# calculator.net
KiCad netlist of a schematic drawn in EAGLE
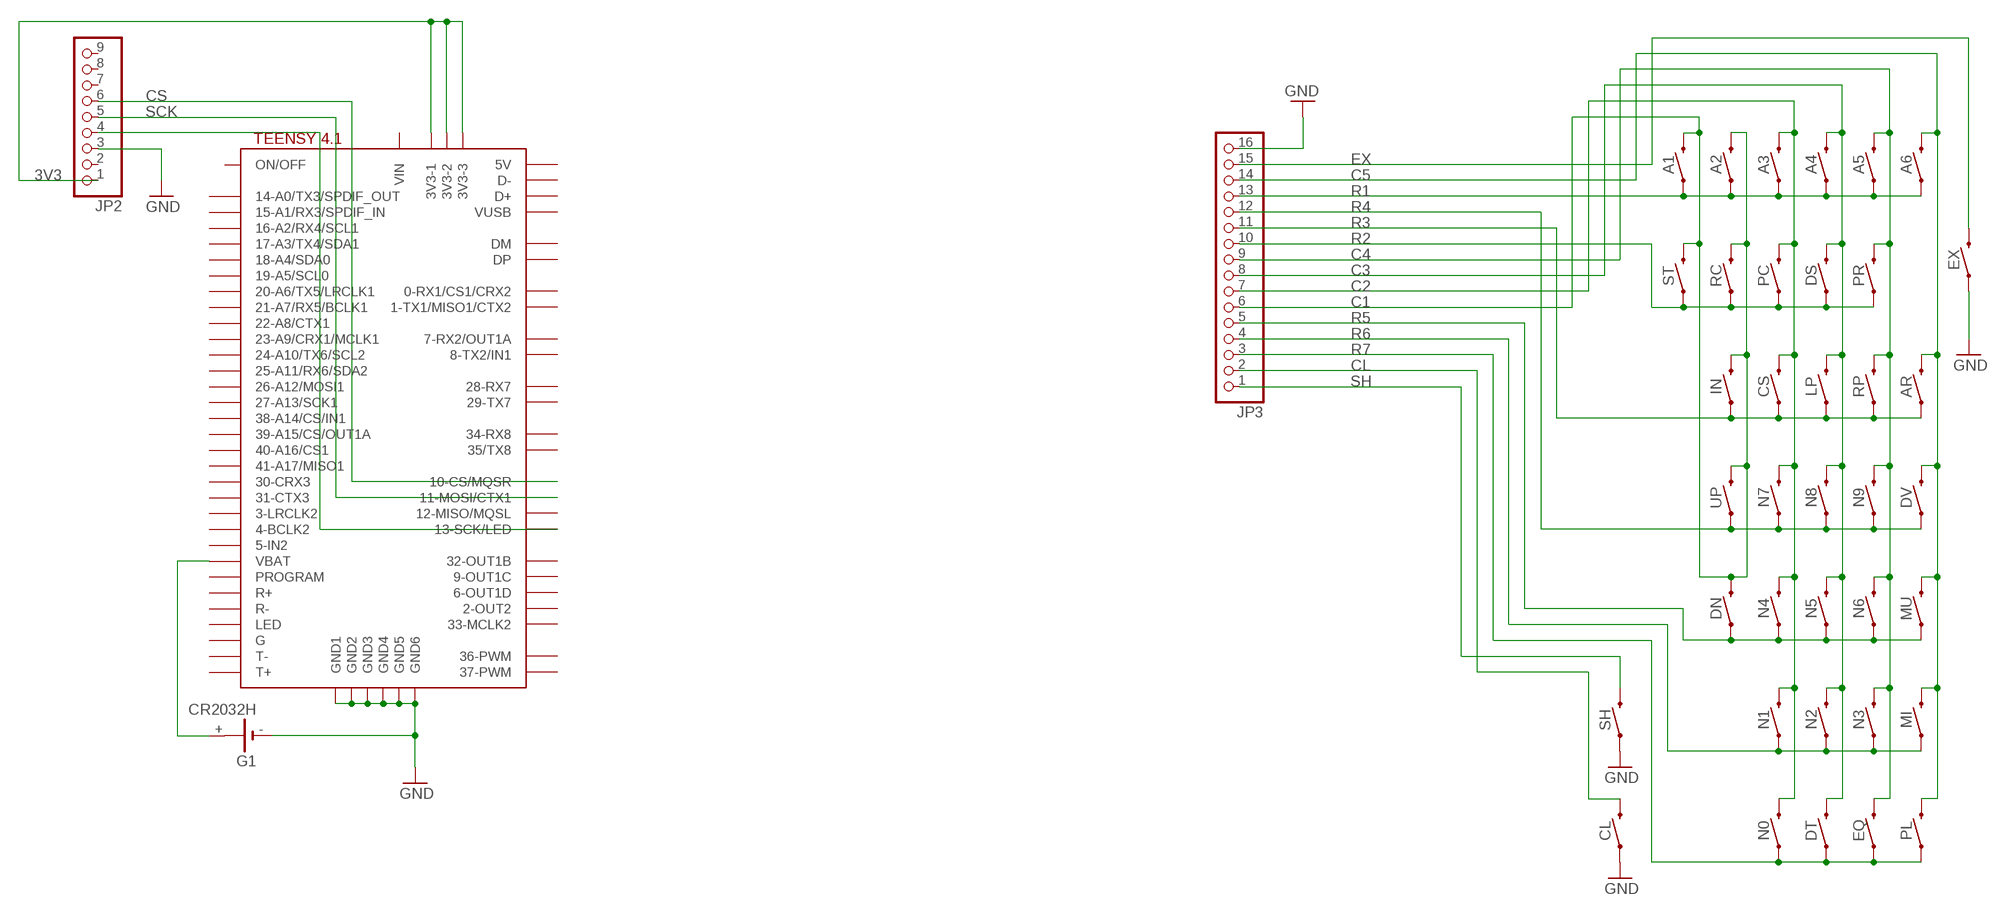
[diagram p0: schematic, sheet 1]

(export (version "E")
  (design (tool "Eeschema 10.0.6"))
  (components
    (comp (ref "A1")
      (value "MOMENTARY-SWITCH-SPST-PTH-6.0MM")
      (footprint "eagle-import:TACTILE_SWITCH_PTH_6.0MM")
      (libsource (lib "eagle-import") (part "MOMENTARY-SWITCH-SPST-PTH-6.0MM"))
    )
    (comp (ref "A2")
      (value "MOMENTARY-SWITCH-SPST-PTH-6.0MM")
      (footprint "eagle-import:TACTILE_SWITCH_PTH_6.0MM")
      (libsource (lib "eagle-import") (part "MOMENTARY-SWITCH-SPST-PTH-6.0MM"))
    )
    (comp (ref "A3")
      (value "MOMENTARY-SWITCH-SPST-PTH-6.0MM")
      (footprint "eagle-import:TACTILE_SWITCH_PTH_6.0MM")
      (libsource (lib "eagle-import") (part "MOMENTARY-SWITCH-SPST-PTH-6.0MM"))
    )
    (comp (ref "A4")
      (value "MOMENTARY-SWITCH-SPST-PTH-6.0MM")
      (footprint "eagle-import:TACTILE_SWITCH_PTH_6.0MM")
      (libsource (lib "eagle-import") (part "MOMENTARY-SWITCH-SPST-PTH-6.0MM"))
    )
    (comp (ref "A5")
      (value "MOMENTARY-SWITCH-SPST-PTH-6.0MM")
      (footprint "eagle-import:TACTILE_SWITCH_PTH_6.0MM")
      (libsource (lib "eagle-import") (part "MOMENTARY-SWITCH-SPST-PTH-6.0MM"))
    )
    (comp (ref "A6")
      (value "MOMENTARY-SWITCH-SPST-PTH-6.0MM")
      (footprint "eagle-import:TACTILE_SWITCH_PTH_6.0MM")
      (libsource (lib "eagle-import") (part "MOMENTARY-SWITCH-SPST-PTH-6.0MM"))
    )
    (comp (ref "AR")
      (value "MOMENTARY-SWITCH-SPST-PTH-6.0MM")
      (footprint "eagle-import:TACTILE_SWITCH_PTH_6.0MM")
      (libsource (lib "eagle-import") (part "MOMENTARY-SWITCH-SPST-PTH-6.0MM"))
    )
    (comp (ref "CL")
      (value "MOMENTARY-SWITCH-SPST-PTH-6.0MM")
      (footprint "eagle-import:TACTILE_SWITCH_PTH_6.0MM")
      (libsource (lib "eagle-import") (part "MOMENTARY-SWITCH-SPST-PTH-6.0MM"))
    )
    (comp (ref "CS")
      (value "MOMENTARY-SWITCH-SPST-PTH-6.0MM")
      (footprint "eagle-import:TACTILE_SWITCH_PTH_6.0MM")
      (libsource (lib "eagle-import") (part "MOMENTARY-SWITCH-SPST-PTH-6.0MM"))
    )
    (comp (ref "DN")
      (value "MOMENTARY-SWITCH-SPST-PTH-6.0MM")
      (footprint "eagle-import:TACTILE_SWITCH_PTH_6.0MM")
      (libsource (lib "eagle-import") (part "MOMENTARY-SWITCH-SPST-PTH-6.0MM"))
    )
    (comp (ref "DS")
      (value "MOMENTARY-SWITCH-SPST-PTH-6.0MM")
      (footprint "eagle-import:TACTILE_SWITCH_PTH_6.0MM")
      (libsource (lib "eagle-import") (part "MOMENTARY-SWITCH-SPST-PTH-6.0MM"))
    )
    (comp (ref "DT")
      (value "MOMENTARY-SWITCH-SPST-PTH-6.0MM")
      (footprint "eagle-import:TACTILE_SWITCH_PTH_6.0MM")
      (libsource (lib "eagle-import") (part "MOMENTARY-SWITCH-SPST-PTH-6.0MM"))
    )
    (comp (ref "DV")
      (value "MOMENTARY-SWITCH-SPST-PTH-6.0MM")
      (footprint "eagle-import:TACTILE_SWITCH_PTH_6.0MM")
      (libsource (lib "eagle-import") (part "MOMENTARY-SWITCH-SPST-PTH-6.0MM"))
    )
    (comp (ref "EQ")
      (value "MOMENTARY-SWITCH-SPST-PTH-6.0MM")
      (footprint "eagle-import:TACTILE_SWITCH_PTH_6.0MM")
      (libsource (lib "eagle-import") (part "MOMENTARY-SWITCH-SPST-PTH-6.0MM"))
    )
    (comp (ref "EX")
      (value "MOMENTARY-SWITCH-SPST-PTH-6.0MM")
      (footprint "eagle-import:TACTILE_SWITCH_PTH_6.0MM")
      (libsource (lib "eagle-import") (part "MOMENTARY-SWITCH-SPST-PTH-6.0MM"))
    )
    (comp (ref "G1")
      (value "CR2032H")
      (footprint "eagle-import:CR2032H")
      (libsource (lib "eagle-import") (part "CR2032H"))
    )
    (comp (ref "IN")
      (value "MOMENTARY-SWITCH-SPST-PTH-6.0MM")
      (footprint "eagle-import:TACTILE_SWITCH_PTH_6.0MM")
      (libsource (lib "eagle-import") (part "MOMENTARY-SWITCH-SPST-PTH-6.0MM"))
    )
    (comp (ref "JP2")
      (value "PINHD-1X9")
      (footprint "eagle-import:1X09-BIG")
      (libsource (lib "eagle-import") (part "PINHD-1X9"))
    )
    (comp (ref "JP3")
      (value "PINHD-1X16")
      (footprint "eagle-import:1X16")
      (libsource (lib "eagle-import") (part "PINHD-1X16"))
    )
    (comp (ref "LP")
      (value "MOMENTARY-SWITCH-SPST-PTH-6.0MM")
      (footprint "eagle-import:TACTILE_SWITCH_PTH_6.0MM")
      (libsource (lib "eagle-import") (part "MOMENTARY-SWITCH-SPST-PTH-6.0MM"))
    )
    (comp (ref "MI")
      (value "MOMENTARY-SWITCH-SPST-PTH-6.0MM")
      (footprint "eagle-import:TACTILE_SWITCH_PTH_6.0MM")
      (libsource (lib "eagle-import") (part "MOMENTARY-SWITCH-SPST-PTH-6.0MM"))
    )
    (comp (ref "MU")
      (value "MOMENTARY-SWITCH-SPST-PTH-6.0MM")
      (footprint "eagle-import:TACTILE_SWITCH_PTH_6.0MM")
      (libsource (lib "eagle-import") (part "MOMENTARY-SWITCH-SPST-PTH-6.0MM"))
    )
    (comp (ref "N0")
      (value "MOMENTARY-SWITCH-SPST-PTH-6.0MM")
      (footprint "eagle-import:TACTILE_SWITCH_PTH_6.0MM")
      (libsource (lib "eagle-import") (part "MOMENTARY-SWITCH-SPST-PTH-6.0MM"))
    )
    (comp (ref "N1")
      (value "MOMENTARY-SWITCH-SPST-PTH-6.0MM")
      (footprint "eagle-import:TACTILE_SWITCH_PTH_6.0MM")
      (libsource (lib "eagle-import") (part "MOMENTARY-SWITCH-SPST-PTH-6.0MM"))
    )
    (comp (ref "N2")
      (value "MOMENTARY-SWITCH-SPST-PTH-6.0MM")
      (footprint "eagle-import:TACTILE_SWITCH_PTH_6.0MM")
      (libsource (lib "eagle-import") (part "MOMENTARY-SWITCH-SPST-PTH-6.0MM"))
    )
    (comp (ref "N3")
      (value "MOMENTARY-SWITCH-SPST-PTH-6.0MM")
      (footprint "eagle-import:TACTILE_SWITCH_PTH_6.0MM")
      (libsource (lib "eagle-import") (part "MOMENTARY-SWITCH-SPST-PTH-6.0MM"))
    )
    (comp (ref "N4")
      (value "MOMENTARY-SWITCH-SPST-PTH-6.0MM")
      (footprint "eagle-import:TACTILE_SWITCH_PTH_6.0MM")
      (libsource (lib "eagle-import") (part "MOMENTARY-SWITCH-SPST-PTH-6.0MM"))
    )
    (comp (ref "N5")
      (value "MOMENTARY-SWITCH-SPST-PTH-6.0MM")
      (footprint "eagle-import:TACTILE_SWITCH_PTH_6.0MM")
      (libsource (lib "eagle-import") (part "MOMENTARY-SWITCH-SPST-PTH-6.0MM"))
    )
    (comp (ref "N6")
      (value "MOMENTARY-SWITCH-SPST-PTH-6.0MM")
      (footprint "eagle-import:TACTILE_SWITCH_PTH_6.0MM")
      (libsource (lib "eagle-import") (part "MOMENTARY-SWITCH-SPST-PTH-6.0MM"))
    )
    (comp (ref "N7")
      (value "MOMENTARY-SWITCH-SPST-PTH-6.0MM")
      (footprint "eagle-import:TACTILE_SWITCH_PTH_6.0MM")
      (libsource (lib "eagle-import") (part "MOMENTARY-SWITCH-SPST-PTH-6.0MM"))
    )
    (comp (ref "N8")
      (value "MOMENTARY-SWITCH-SPST-PTH-6.0MM")
      (footprint "eagle-import:TACTILE_SWITCH_PTH_6.0MM")
      (libsource (lib "eagle-import") (part "MOMENTARY-SWITCH-SPST-PTH-6.0MM"))
    )
    (comp (ref "N9")
      (value "MOMENTARY-SWITCH-SPST-PTH-6.0MM")
      (footprint "eagle-import:TACTILE_SWITCH_PTH_6.0MM")
      (libsource (lib "eagle-import") (part "MOMENTARY-SWITCH-SPST-PTH-6.0MM"))
    )
    (comp (ref "PC")
      (value "MOMENTARY-SWITCH-SPST-PTH-6.0MM")
      (footprint "eagle-import:TACTILE_SWITCH_PTH_6.0MM")
      (libsource (lib "eagle-import") (part "MOMENTARY-SWITCH-SPST-PTH-6.0MM"))
    )
    (comp (ref "PL")
      (value "MOMENTARY-SWITCH-SPST-PTH-6.0MM")
      (footprint "eagle-import:TACTILE_SWITCH_PTH_6.0MM")
      (libsource (lib "eagle-import") (part "MOMENTARY-SWITCH-SPST-PTH-6.0MM"))
    )
    (comp (ref "PR")
      (value "MOMENTARY-SWITCH-SPST-PTH-6.0MM")
      (footprint "eagle-import:TACTILE_SWITCH_PTH_6.0MM")
      (libsource (lib "eagle-import") (part "MOMENTARY-SWITCH-SPST-PTH-6.0MM"))
    )
    (comp (ref "RC")
      (value "MOMENTARY-SWITCH-SPST-PTH-6.0MM")
      (footprint "eagle-import:TACTILE_SWITCH_PTH_6.0MM")
      (libsource (lib "eagle-import") (part "MOMENTARY-SWITCH-SPST-PTH-6.0MM"))
    )
    (comp (ref "RP")
      (value "MOMENTARY-SWITCH-SPST-PTH-6.0MM")
      (footprint "eagle-import:TACTILE_SWITCH_PTH_6.0MM")
      (libsource (lib "eagle-import") (part "MOMENTARY-SWITCH-SPST-PTH-6.0MM"))
    )
    (comp (ref "SH")
      (value "MOMENTARY-SWITCH-SPST-PTH-6.0MM")
      (footprint "eagle-import:TACTILE_SWITCH_PTH_6.0MM")
      (libsource (lib "eagle-import") (part "MOMENTARY-SWITCH-SPST-PTH-6.0MM"))
    )
    (comp (ref "ST")
      (value "MOMENTARY-SWITCH-SPST-PTH-6.0MM")
      (footprint "eagle-import:TACTILE_SWITCH_PTH_6.0MM")
      (libsource (lib "eagle-import") (part "MOMENTARY-SWITCH-SPST-PTH-6.0MM"))
    )
    (comp (ref "U$1")
      (value "TEENSY41")
      (footprint "eagle-import:TEENSY41")
      (libsource (lib "eagle-import") (part "TEENSY41"))
    )
    (comp (ref "UP")
      (value "MOMENTARY-SWITCH-SPST-PTH-6.0MM")
      (footprint "eagle-import:TACTILE_SWITCH_PTH_6.0MM")
      (libsource (lib "eagle-import") (part "MOMENTARY-SWITCH-SPST-PTH-6.0MM"))
    )
  )
  (nets
    (net (code "1") (name "/3V3") (class "Default")
      (node (ref "JP2") (pin "1") (pinfunction "1_1") (pintype "passive"))
      (node (ref "U$1") (pin "3V3-1") (pinfunction "3V3-1_3V3-1") (pintype "bidirectional"))
      (node (ref "U$1") (pin "3V3-2") (pinfunction "3V3-2_3V3-2") (pintype "bidirectional"))
      (node (ref "U$1") (pin "3V3-3") (pinfunction "3V3-3_3V3-3") (pintype "bidirectional"))
    )
    (net (code "2") (name "/C1") (class "Default")
      (node (ref "A1") (pin "3") (pinfunction "2_3") (pintype "passive"))
      (node (ref "A2") (pin "3") (pinfunction "2_3") (pintype "passive"))
      (node (ref "DN") (pin "3") (pinfunction "2_3") (pintype "passive"))
      (node (ref "IN") (pin "3") (pinfunction "2_3") (pintype "passive"))
      (node (ref "JP3") (pin "6") (pinfunction "6_6") (pintype "passive"))
      (node (ref "RC") (pin "3") (pinfunction "2_3") (pintype "passive"))
      (node (ref "ST") (pin "3") (pinfunction "2_3") (pintype "passive"))
      (node (ref "UP") (pin "3") (pinfunction "2_3") (pintype "passive"))
    )
    (net (code "3") (name "/C2") (class "Default")
      (node (ref "A3") (pin "3") (pinfunction "2_3") (pintype "passive"))
      (node (ref "CS") (pin "3") (pinfunction "2_3") (pintype "passive"))
      (node (ref "JP3") (pin "7") (pinfunction "7_7") (pintype "passive"))
      (node (ref "N0") (pin "3") (pinfunction "2_3") (pintype "passive"))
      (node (ref "N1") (pin "3") (pinfunction "2_3") (pintype "passive"))
      (node (ref "N4") (pin "3") (pinfunction "2_3") (pintype "passive"))
      (node (ref "N7") (pin "3") (pinfunction "2_3") (pintype "passive"))
      (node (ref "PC") (pin "3") (pinfunction "2_3") (pintype "passive"))
    )
    (net (code "4") (name "/C3") (class "Default")
      (node (ref "A4") (pin "3") (pinfunction "2_3") (pintype "passive"))
      (node (ref "DS") (pin "3") (pinfunction "2_3") (pintype "passive"))
      (node (ref "DT") (pin "3") (pinfunction "2_3") (pintype "passive"))
      (node (ref "JP3") (pin "8") (pinfunction "8_8") (pintype "passive"))
      (node (ref "LP") (pin "3") (pinfunction "2_3") (pintype "passive"))
      (node (ref "N2") (pin "3") (pinfunction "2_3") (pintype "passive"))
      (node (ref "N5") (pin "3") (pinfunction "2_3") (pintype "passive"))
      (node (ref "N8") (pin "3") (pinfunction "2_3") (pintype "passive"))
    )
    (net (code "5") (name "/C4") (class "Default")
      (node (ref "A5") (pin "3") (pinfunction "2_3") (pintype "passive"))
      (node (ref "EQ") (pin "3") (pinfunction "2_3") (pintype "passive"))
      (node (ref "JP3") (pin "9") (pinfunction "9_9") (pintype "passive"))
      (node (ref "N3") (pin "3") (pinfunction "2_3") (pintype "passive"))
      (node (ref "N6") (pin "3") (pinfunction "2_3") (pintype "passive"))
      (node (ref "N9") (pin "3") (pinfunction "2_3") (pintype "passive"))
      (node (ref "PR") (pin "3") (pinfunction "2_3") (pintype "passive"))
      (node (ref "RP") (pin "3") (pinfunction "2_3") (pintype "passive"))
    )
    (net (code "6") (name "/C5") (class "Default")
      (node (ref "A6") (pin "3") (pinfunction "2_3") (pintype "passive"))
      (node (ref "AR") (pin "3") (pinfunction "2_3") (pintype "passive"))
      (node (ref "DV") (pin "3") (pinfunction "2_3") (pintype "passive"))
      (node (ref "JP3") (pin "14") (pinfunction "14_14") (pintype "passive"))
      (node (ref "MI") (pin "3") (pinfunction "2_3") (pintype "passive"))
      (node (ref "MU") (pin "3") (pinfunction "2_3") (pintype "passive"))
      (node (ref "PL") (pin "3") (pinfunction "2_3") (pintype "passive"))
    )
    (net (code "7") (name "/CL") (class "Default")
      (node (ref "CL") (pin "3") (pinfunction "2_3") (pintype "passive"))
      (node (ref "JP3") (pin "2") (pinfunction "2_2") (pintype "passive"))
    )
    (net (code "8") (name "/CS") (class "Default")
      (node (ref "JP2") (pin "6") (pinfunction "6_6") (pintype "passive"))
      (node (ref "U$1") (pin "10-CS\\MQSR") (pinfunction "10-CS/MQSR_10-CS\\MQSR") (pintype "bidirectional"))
    )
    (net (code "9") (name "/EX") (class "Default")
      (node (ref "EX") (pin "3") (pinfunction "2_3") (pintype "passive"))
      (node (ref "JP3") (pin "15") (pinfunction "15_15") (pintype "passive"))
    )
    (net (code "10") (name "/R1") (class "Default")
      (node (ref "A1") (pin "1") (pinfunction "1_1") (pintype "passive"))
      (node (ref "A2") (pin "1") (pinfunction "1_1") (pintype "passive"))
      (node (ref "A3") (pin "1") (pinfunction "1_1") (pintype "passive"))
      (node (ref "A4") (pin "1") (pinfunction "1_1") (pintype "passive"))
      (node (ref "A5") (pin "1") (pinfunction "1_1") (pintype "passive"))
      (node (ref "A6") (pin "1") (pinfunction "1_1") (pintype "passive"))
      (node (ref "JP3") (pin "13") (pinfunction "13_13") (pintype "passive"))
    )
    (net (code "11") (name "/R2") (class "Default")
      (node (ref "DS") (pin "1") (pinfunction "1_1") (pintype "passive"))
      (node (ref "JP3") (pin "10") (pinfunction "10_10") (pintype "passive"))
      (node (ref "PC") (pin "1") (pinfunction "1_1") (pintype "passive"))
      (node (ref "PR") (pin "1") (pinfunction "1_1") (pintype "passive"))
      (node (ref "RC") (pin "1") (pinfunction "1_1") (pintype "passive"))
      (node (ref "ST") (pin "1") (pinfunction "1_1") (pintype "passive"))
    )
    (net (code "12") (name "/R3") (class "Default")
      (node (ref "AR") (pin "1") (pinfunction "1_1") (pintype "passive"))
      (node (ref "CS") (pin "1") (pinfunction "1_1") (pintype "passive"))
      (node (ref "IN") (pin "1") (pinfunction "1_1") (pintype "passive"))
      (node (ref "JP3") (pin "11") (pinfunction "11_11") (pintype "passive"))
      (node (ref "LP") (pin "1") (pinfunction "1_1") (pintype "passive"))
      (node (ref "RP") (pin "1") (pinfunction "1_1") (pintype "passive"))
    )
    (net (code "13") (name "/R4") (class "Default")
      (node (ref "DV") (pin "1") (pinfunction "1_1") (pintype "passive"))
      (node (ref "JP3") (pin "12") (pinfunction "12_12") (pintype "passive"))
      (node (ref "N7") (pin "1") (pinfunction "1_1") (pintype "passive"))
      (node (ref "N8") (pin "1") (pinfunction "1_1") (pintype "passive"))
      (node (ref "N9") (pin "1") (pinfunction "1_1") (pintype "passive"))
      (node (ref "UP") (pin "1") (pinfunction "1_1") (pintype "passive"))
    )
    (net (code "14") (name "/R5") (class "Default")
      (node (ref "DN") (pin "1") (pinfunction "1_1") (pintype "passive"))
      (node (ref "JP3") (pin "5") (pinfunction "5_5") (pintype "passive"))
      (node (ref "MU") (pin "1") (pinfunction "1_1") (pintype "passive"))
      (node (ref "N4") (pin "1") (pinfunction "1_1") (pintype "passive"))
      (node (ref "N5") (pin "1") (pinfunction "1_1") (pintype "passive"))
      (node (ref "N6") (pin "1") (pinfunction "1_1") (pintype "passive"))
    )
    (net (code "15") (name "/R6") (class "Default")
      (node (ref "JP3") (pin "4") (pinfunction "4_4") (pintype "passive"))
      (node (ref "MI") (pin "1") (pinfunction "1_1") (pintype "passive"))
      (node (ref "N1") (pin "1") (pinfunction "1_1") (pintype "passive"))
      (node (ref "N2") (pin "1") (pinfunction "1_1") (pintype "passive"))
      (node (ref "N3") (pin "1") (pinfunction "1_1") (pintype "passive"))
    )
    (net (code "16") (name "/R7") (class "Default")
      (node (ref "DT") (pin "1") (pinfunction "1_1") (pintype "passive"))
      (node (ref "EQ") (pin "1") (pinfunction "1_1") (pintype "passive"))
      (node (ref "JP3") (pin "3") (pinfunction "3_3") (pintype "passive"))
      (node (ref "N0") (pin "1") (pinfunction "1_1") (pintype "passive"))
      (node (ref "PL") (pin "1") (pinfunction "1_1") (pintype "passive"))
    )
    (net (code "17") (name "/SCK") (class "Default")
      (node (ref "JP2") (pin "4") (pinfunction "4_4") (pintype "passive"))
      (node (ref "U$1") (pin "13-SCK/LED") (pinfunction "13-SCK/LED_13-SCK/LED") (pintype "bidirectional"))
    )
    (net (code "18") (name "/SH") (class "Default")
      (node (ref "JP3") (pin "1") (pinfunction "1_1") (pintype "passive"))
      (node (ref "SH") (pin "3") (pinfunction "2_3") (pintype "passive"))
    )
    (net (code "19") (name "GND") (class "Default")
      (node (ref "CL") (pin "1") (pinfunction "1_1") (pintype "passive"))
      (node (ref "EX") (pin "1") (pinfunction "1_1") (pintype "passive"))
      (node (ref "G1") (pin "-") (pinfunction "-_-") (pintype "passive"))
      (node (ref "JP2") (pin "3") (pinfunction "3_3") (pintype "passive"))
      (node (ref "JP3") (pin "16") (pinfunction "16_16") (pintype "passive"))
      (node (ref "SH") (pin "1") (pinfunction "1_1") (pintype "passive"))
      (node (ref "U$1") (pin "GND1") (pinfunction "GND1_GND1") (pintype "bidirectional"))
      (node (ref "U$1") (pin "GND2") (pinfunction "GND2_GND2") (pintype "bidirectional"))
      (node (ref "U$1") (pin "GND3") (pinfunction "GND3_GND3") (pintype "bidirectional"))
      (node (ref "U$1") (pin "GND4") (pinfunction "GND4_GND4") (pintype "bidirectional"))
      (node (ref "U$1") (pin "GND5") (pinfunction "GND5_GND5") (pintype "bidirectional"))
      (node (ref "U$1") (pin "GND6") (pinfunction "GND6_GND6") (pintype "bidirectional"))
    )
    (net (code "20") (name "Net-(G1-Pad+)") (class "Default")
      (node (ref "G1") (pin "+") (pinfunction "+_+") (pintype "passive"))
      (node (ref "U$1") (pin "VBAT") (pinfunction "VBAT_VBAT") (pintype "bidirectional"))
    )
    (net (code "21") (name "Net-(JP2-Pad5)") (class "Default")
      (node (ref "JP2") (pin "5") (pinfunction "5_5") (pintype "passive"))
      (node (ref "U$1") (pin "11-MOSI/CTX1") (pinfunction "11-MOSI/CTX1_11-MOSI/CTX1") (pintype "bidirectional"))
    )
    (net (code "22") (name "unconnected-(G1-+-Pad+@1)") (class "Default")
      (node (ref "G1") (pin "+@1") (pinfunction "+_+@1") (pintype "passive"))
    )
    (net (code "23") (name "unconnected-(JP2-Pad2)") (class "Default")
      (node (ref "JP2") (pin "2") (pinfunction "2_2") (pintype "passive"))
    )
    (net (code "24") (name "unconnected-(JP2-Pad7)") (class "Default")
      (node (ref "JP2") (pin "7") (pinfunction "7_7") (pintype "passive"))
    )
    (net (code "25") (name "unconnected-(JP2-Pad8)") (class "Default")
      (node (ref "JP2") (pin "8") (pinfunction "8_8") (pintype "passive"))
    )
    (net (code "26") (name "unconnected-(JP2-Pad9)") (class "Default")
      (node (ref "JP2") (pin "9") (pinfunction "9_9") (pintype "passive"))
    )
    (net (code "27") (name "unconnected-(U$1-5V-Pad+5V)") (class "Default")
      (node (ref "U$1") (pin "+5V") (pinfunction "5V_+5V") (pintype "bidirectional"))
    )
    (net (code "28") (name "unconnected-(U$1-8-TX2{slash}IN1-Pad8-TX2{slash}IN2)") (class "Default")
      (node (ref "U$1") (pin "8-TX2/IN2") (pinfunction "8-TX2/IN1_8-TX2/IN2") (pintype "bidirectional"))
    )
    (net (code "29") (name "unconnected-(U$1-35{slash}TX8-Pad35-TX8)") (class "Default")
      (node (ref "U$1") (pin "35-TX8") (pinfunction "35/TX8_35-TX8") (pintype "bidirectional"))
    )
    (net (code "30") (name "unconnected-(U$1-Pad0-RX1{slash}CS1{slash}CRX2)") (class "Default")
      (node (ref "U$1") (pin "0-RX1/CS1/CRX2") (pinfunction "0-RX1/CS1/CRX2_0-RX1/CS1/CRX2") (pintype "bidirectional"))
    )
    (net (code "31") (name "unconnected-(U$1-Pad1-TX1{slash}MISO1{slash}CTX2)") (class "Default")
      (node (ref "U$1") (pin "1-TX1/MISO1/CTX2") (pinfunction "1-TX1/MISO1/CTX2_1-TX1/MISO1/CTX2") (pintype "bidirectional"))
    )
    (net (code "32") (name "unconnected-(U$1-Pad2-OUT2)") (class "Default")
      (node (ref "U$1") (pin "2-OUT2") (pinfunction "2-OUT2_2-OUT2") (pintype "bidirectional"))
    )
    (net (code "33") (name "unconnected-(U$1-Pad3-LRCLK2)") (class "Default")
      (node (ref "U$1") (pin "3-LRCLK2") (pinfunction "3-LRCLK2_3-LRCLK2") (pintype "bidirectional"))
    )
    (net (code "34") (name "unconnected-(U$1-Pad4-BCLK2)") (class "Default")
      (node (ref "U$1") (pin "4-BCLK2") (pinfunction "4-BCLK2_4-BCLK2") (pintype "bidirectional"))
    )
    (net (code "35") (name "unconnected-(U$1-Pad5-IN2)") (class "Default")
      (node (ref "U$1") (pin "5-IN2") (pinfunction "5-IN2_5-IN2") (pintype "bidirectional"))
    )
    (net (code "36") (name "unconnected-(U$1-Pad6-OUT1D)") (class "Default")
      (node (ref "U$1") (pin "6-OUT1D") (pinfunction "6-OUT1D_6-OUT1D") (pintype "bidirectional"))
    )
    (net (code "37") (name "unconnected-(U$1-Pad7-RX2{slash}OUT1A)") (class "Default")
      (node (ref "U$1") (pin "7-RX2/OUT1A") (pinfunction "7-RX2/OUT1A_7-RX2/OUT1A") (pintype "bidirectional"))
    )
    (net (code "38") (name "unconnected-(U$1-Pad9-OUT1C)") (class "Default")
      (node (ref "U$1") (pin "9-OUT1C") (pinfunction "9-OUT1C_9-OUT1C") (pintype "bidirectional"))
    )
    (net (code "39") (name "unconnected-(U$1-Pad12-MISO{slash}MQSL)") (class "Default")
      (node (ref "U$1") (pin "12-MISO/MQSL") (pinfunction "12-MISO/MQSL_12-MISO/MQSL") (pintype "bidirectional"))
    )
    (net (code "40") (name "unconnected-(U$1-Pad14-A0{slash}TX3{slash}SPDIF_OUT)") (class "Default")
      (node (ref "U$1") (pin "14-A0/TX3/SPDIF_OUT") (pinfunction "14-A0/TX3/SPDIF_OUT_14-A0/TX3/SPDIF_OUT") (pintype "bidirectional"))
    )
    (net (code "41") (name "unconnected-(U$1-Pad15-A1{slash}RX3{slash}SPDIF_IN)") (class "Default")
      (node (ref "U$1") (pin "15-A1/RX3/SPDIF_IN") (pinfunction "15-A1/RX3/SPDIF_IN_15-A1/RX3/SPDIF_IN") (pintype "bidirectional"))
    )
    (net (code "42") (name "unconnected-(U$1-Pad16-A2{slash}RX4{slash}SCL1)") (class "Default")
      (node (ref "U$1") (pin "16-A2/RX4/SCL1") (pinfunction "16-A2/RX4/SCL1_16-A2/RX4/SCL1") (pintype "bidirectional"))
    )
    (net (code "43") (name "unconnected-(U$1-Pad17-A3{slash}TX4{slash}SDA1)") (class "Default")
      (node (ref "U$1") (pin "17-A3/TX4/SDA1") (pinfunction "17-A3/TX4/SDA1_17-A3/TX4/SDA1") (pintype "bidirectional"))
    )
    (net (code "44") (name "unconnected-(U$1-Pad18-A4{slash}SDA0)") (class "Default")
      (node (ref "U$1") (pin "18-A4/SDA0") (pinfunction "18-A4/SDA0_18-A4/SDA0") (pintype "bidirectional"))
    )
    (net (code "45") (name "unconnected-(U$1-Pad19-A5{slash}SCL0)") (class "Default")
      (node (ref "U$1") (pin "19-A5/SCL0") (pinfunction "19-A5/SCL0_19-A5/SCL0") (pintype "bidirectional"))
    )
    (net (code "46") (name "unconnected-(U$1-Pad20-A6{slash}TX5{slash}LRCLK1)") (class "Default")
      (node (ref "U$1") (pin "20-A6/TX5/LRCLK1") (pinfunction "20-A6/TX5/LRCLK1_20-A6/TX5/LRCLK1") (pintype "bidirectional"))
    )
    (net (code "47") (name "unconnected-(U$1-Pad21-A7{slash}RX5{slash}BCLK1)") (class "Default")
      (node (ref "U$1") (pin "21-A7/RX5/BCLK1") (pinfunction "21-A7/RX5/BCLK1_21-A7/RX5/BCLK1") (pintype "bidirectional"))
    )
    (net (code "48") (name "unconnected-(U$1-Pad22-A8{slash}CTX1)") (class "Default")
      (node (ref "U$1") (pin "22-A8/CTX1") (pinfunction "22-A8/CTX1_22-A8/CTX1") (pintype "bidirectional"))
    )
    (net (code "49") (name "unconnected-(U$1-Pad23-A9{slash}CRX1{slash}MCLK1)") (class "Default")
      (node (ref "U$1") (pin "23-A9/CRX1/MCLK1") (pinfunction "23-A9/CRX1/MCLK1_23-A9/CRX1/MCLK1") (pintype "bidirectional"))
    )
    (net (code "50") (name "unconnected-(U$1-Pad24-A10{slash}TX6{slash}SCL2)") (class "Default")
      (node (ref "U$1") (pin "24-A10/TX6/SCL2") (pinfunction "24-A10/TX6/SCL2_24-A10/TX6/SCL2") (pintype "bidirectional"))
    )
    (net (code "51") (name "unconnected-(U$1-Pad25-A11{slash}RX6{slash}SDA2)") (class "Default")
      (node (ref "U$1") (pin "25-A11/RX6/SDA2") (pinfunction "25-A11/RX6/SDA2_25-A11/RX6/SDA2") (pintype "bidirectional"))
    )
    (net (code "52") (name "unconnected-(U$1-Pad26-A12{slash}MOSI1)") (class "Default")
      (node (ref "U$1") (pin "26-A12/MOSI1") (pinfunction "26-A12/MOSI1_26-A12/MOSI1") (pintype "bidirectional"))
    )
    (net (code "53") (name "unconnected-(U$1-Pad27-A13{slash}SCK1)") (class "Default")
      (node (ref "U$1") (pin "27-A13/SCK1") (pinfunction "27-A13/SCK1_27-A13/SCK1") (pintype "bidirectional"))
    )
    (net (code "54") (name "unconnected-(U$1-Pad28-RX7)") (class "Default")
      (node (ref "U$1") (pin "28-RX7") (pinfunction "28-RX7_28-RX7") (pintype "bidirectional"))
    )
    (net (code "55") (name "unconnected-(U$1-Pad29-TX7)") (class "Default")
      (node (ref "U$1") (pin "29-TX7") (pinfunction "29-TX7_29-TX7") (pintype "bidirectional"))
    )
    (net (code "56") (name "unconnected-(U$1-Pad30-CRX3)") (class "Default")
      (node (ref "U$1") (pin "30-CRX3") (pinfunction "30-CRX3_30-CRX3") (pintype "bidirectional"))
    )
    (net (code "57") (name "unconnected-(U$1-Pad31-CTX3)") (class "Default")
      (node (ref "U$1") (pin "31-CTX3") (pinfunction "31-CTX3_31-CTX3") (pintype "bidirectional"))
    )
    (net (code "58") (name "unconnected-(U$1-Pad32-OUT1B)") (class "Default")
      (node (ref "U$1") (pin "32-OUT1B") (pinfunction "32-OUT1B_32-OUT1B") (pintype "bidirectional"))
    )
    (net (code "59") (name "unconnected-(U$1-Pad33-MCLK2)") (class "Default")
      (node (ref "U$1") (pin "33-MCLK2") (pinfunction "33-MCLK2_33-MCLK2") (pintype "bidirectional"))
    )
    (net (code "60") (name "unconnected-(U$1-Pad34-RX8)") (class "Default")
      (node (ref "U$1") (pin "34-RX8") (pinfunction "34-RX8_34-RX8") (pintype "bidirectional"))
    )
    (net (code "61") (name "unconnected-(U$1-Pad36-PWM)") (class "Default")
      (node (ref "U$1") (pin "36-PWM") (pinfunction "36-PWM_36-PWM") (pintype "bidirectional"))
    )
    (net (code "62") (name "unconnected-(U$1-Pad37-PWM)") (class "Default")
      (node (ref "U$1") (pin "37-PWM") (pinfunction "37-PWM_37-PWM") (pintype "bidirectional"))
    )
    (net (code "63") (name "unconnected-(U$1-Pad38-A14{slash}CS{slash}IN1)") (class "Default")
      (node (ref "U$1") (pin "38-A14/CS/IN1") (pinfunction "38-A14/CS/IN1_38-A14/CS/IN1") (pintype "bidirectional"))
    )
    (net (code "64") (name "unconnected-(U$1-Pad39-A15{slash}CS{slash}OUT1A)") (class "Default")
      (node (ref "U$1") (pin "39-A15/CS/OUT1A") (pinfunction "39-A15/CS/OUT1A_39-A15/CS/OUT1A") (pintype "bidirectional"))
    )
    (net (code "65") (name "unconnected-(U$1-Pad40-A16{slash}CS1)") (class "Default")
      (node (ref "U$1") (pin "40-A16/CS1") (pinfunction "40-A16/CS1_40-A16/CS1") (pintype "bidirectional"))
    )
    (net (code "66") (name "unconnected-(U$1-Pad41-A17{slash}MISO1)") (class "Default")
      (node (ref "U$1") (pin "41-A17/MISO1") (pinfunction "41-A17/MISO1_41-A17/MISO1") (pintype "bidirectional"))
    )
    (net (code "67") (name "unconnected-(U$1-PadD+)") (class "Default")
      (node (ref "U$1") (pin "D+") (pinfunction "D+_D+") (pintype "bidirectional"))
    )
    (net (code "68") (name "unconnected-(U$1-PadD-)") (class "Default")
      (node (ref "U$1") (pin "D-") (pinfunction "D-_D-") (pintype "bidirectional"))
    )
    (net (code "69") (name "unconnected-(U$1-PadDM)") (class "Default")
      (node (ref "U$1") (pin "DM") (pinfunction "DM_DM") (pintype "bidirectional"))
    )
    (net (code "70") (name "unconnected-(U$1-PadDP)") (class "Default")
      (node (ref "U$1") (pin "DP") (pinfunction "DP_DP") (pintype "bidirectional"))
    )
    (net (code "71") (name "unconnected-(U$1-PadG)") (class "Default")
      (node (ref "U$1") (pin "G") (pinfunction "G_G") (pintype "bidirectional"))
    )
    (net (code "72") (name "unconnected-(U$1-PadLED)") (class "Default")
      (node (ref "U$1") (pin "LED") (pinfunction "LED_LED") (pintype "bidirectional"))
    )
    (net (code "73") (name "unconnected-(U$1-PadON{slash}OFF)") (class "Default")
      (node (ref "U$1") (pin "ON/OFF") (pinfunction "ON/OFF_ON/OFF") (pintype "bidirectional"))
    )
    (net (code "74") (name "unconnected-(U$1-PadPROGRAM)") (class "Default")
      (node (ref "U$1") (pin "PROGRAM") (pinfunction "PROGRAM_PROGRAM") (pintype "bidirectional"))
    )
    (net (code "75") (name "unconnected-(U$1-PadR+)") (class "Default")
      (node (ref "U$1") (pin "R+") (pinfunction "R+_R+") (pintype "bidirectional"))
    )
    (net (code "76") (name "unconnected-(U$1-PadR-)") (class "Default")
      (node (ref "U$1") (pin "R-") (pinfunction "R-_R-") (pintype "bidirectional"))
    )
    (net (code "77") (name "unconnected-(U$1-PadT+)") (class "Default")
      (node (ref "U$1") (pin "T+") (pinfunction "T+_T+") (pintype "bidirectional"))
    )
    (net (code "78") (name "unconnected-(U$1-PadT-)") (class "Default")
      (node (ref "U$1") (pin "T-") (pinfunction "T-_T-") (pintype "bidirectional"))
    )
    (net (code "79") (name "unconnected-(U$1-PadVIN)") (class "Default")
      (node (ref "U$1") (pin "VIN") (pinfunction "VIN_VIN") (pintype "bidirectional"))
    )
    (net (code "80") (name "unconnected-(U$1-PadVUSB)") (class "Default")
      (node (ref "U$1") (pin "VUSB") (pinfunction "VUSB_VUSB") (pintype "bidirectional"))
    )
  )
)
